# MCU_USB.net
KiCad netlist of a schematic drawn in Altium Designer
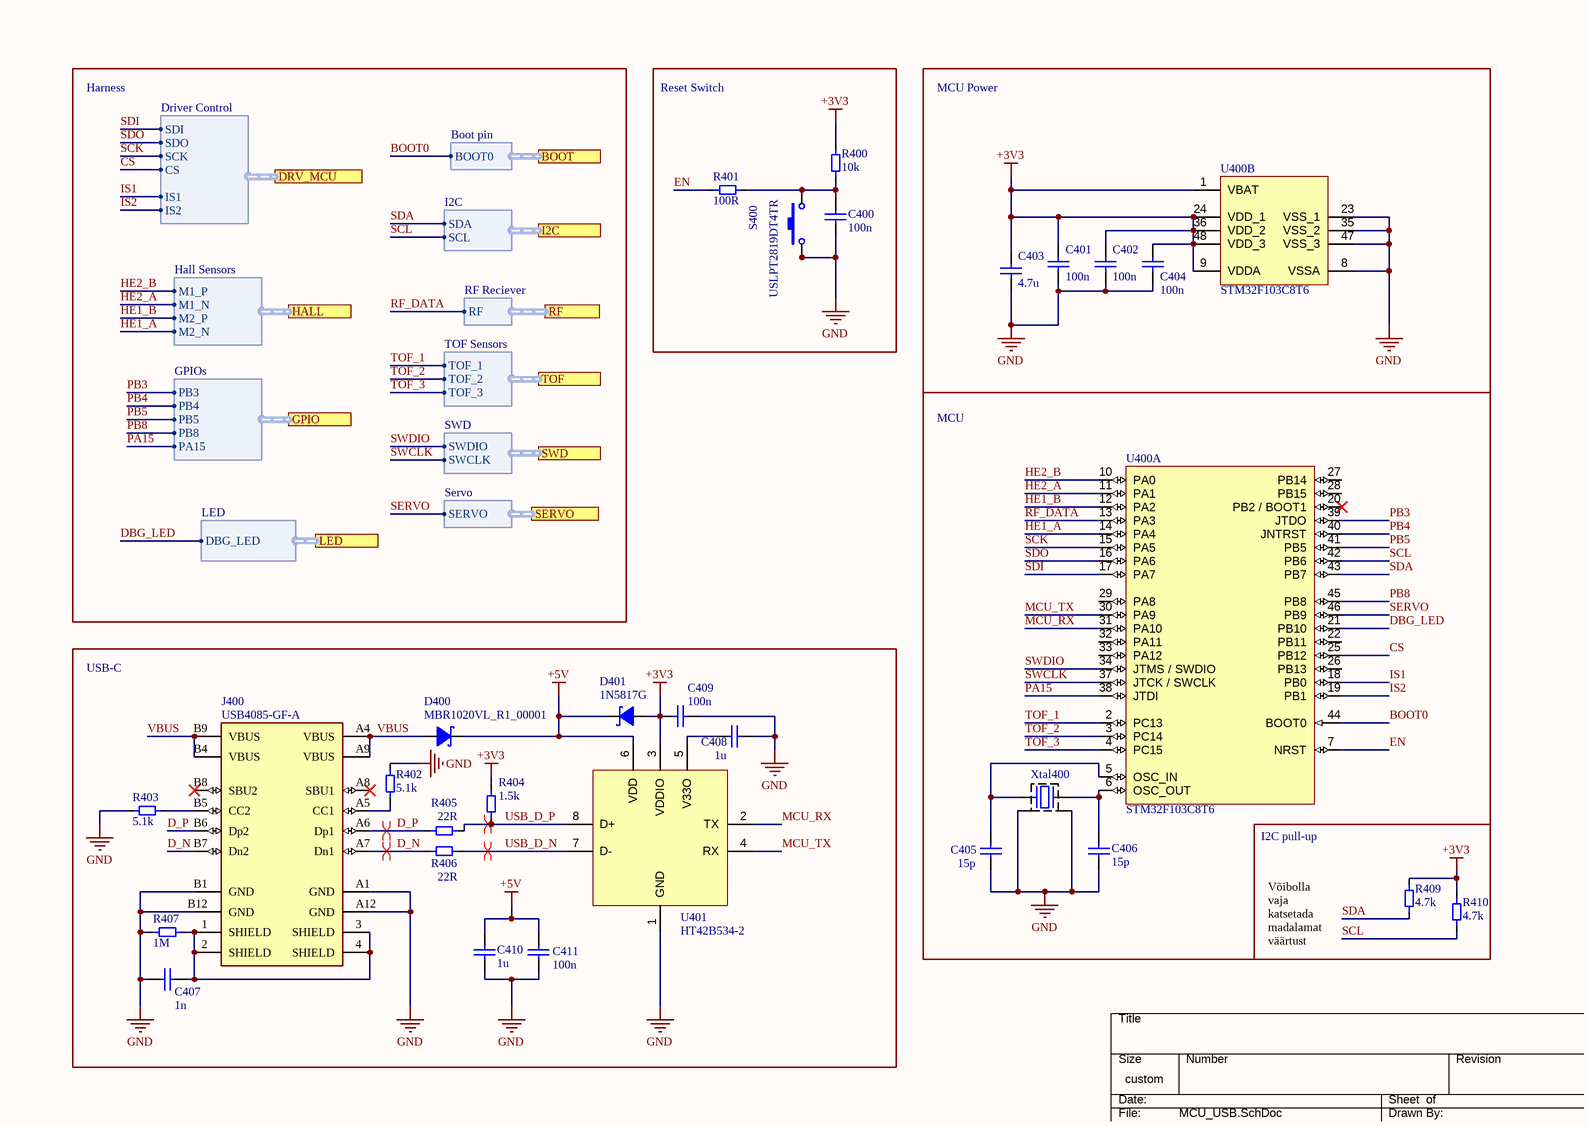
[diagram p0: MCU_USB.SchDoc]

(export (version "E")
  (design (tool "Eeschema 10.0.6"))
  (components
    (comp (ref "C400")
      (value "100n")
      (footprint "MLCC_0603_M")
      (description "MLCC, 0603, 100n, 10%, 50V, X7R")
      (fields (field (name "VOLTAGE") "50V") (field (name "TOLERANCE") "10%"))
      (libsource (lib "Krakul Vault") (part "CAPACITOR_NONPOL_IEC"))
    )
    (comp (ref "C401")
      (value "100n")
      (footprint "MLCC_0603_M")
      (description "MLCC, 0603, 100n, 10%, 50V, X7R")
      (fields (field (name "VOLTAGE") "50V") (field (name "TOLERANCE") "10%"))
      (libsource (lib "Krakul Vault") (part "CAPACITOR_NONPOL_IEC"))
    )
    (comp (ref "C402")
      (value "100n")
      (footprint "MLCC_0603_M")
      (description "MLCC, 0603, 100n, 10%, 50V, X7R")
      (fields (field (name "VOLTAGE") "50V") (field (name "TOLERANCE") "10%"))
      (libsource (lib "Krakul Vault") (part "CAPACITOR_NONPOL_IEC"))
    )
    (comp (ref "C403")
      (value "4.7u")
      (footprint "MLCC_0805_M")
      (description "MLCC, 0805, 4.7u, 20%, 50V, X5R")
      (fields (field (name "MANUFACTURER") "Any") (field (name "VOLTAGE") "50V"))
      (libsource (lib "Krakul Vault") (part "CAPACITOR_NONPOL_IEC"))
    )
    (comp (ref "C404")
      (value "100n")
      (footprint "MLCC_0603_M")
      (description "MLCC, 0603, 100n, 10%, 50V, X7R")
      (fields (field (name "VOLTAGE") "50V") (field (name "TOLERANCE") "10%"))
      (libsource (lib "Krakul Vault") (part "CAPACITOR_NONPOL_IEC"))
    )
    (comp (ref "C405")
      (value "15p")
      (footprint "MLCC_0402_M")
      (description "MLCC, 0402, 15p, 10%, 25V, C0G/NP0")
      (fields (field (name "MANUFACTURER") "Any") (field (name "TOLERANCE") "10%"))
      (libsource (lib "Krakul Vault") (part "CAPACITOR_NONPOL_IEC"))
    )
    (comp (ref "C406")
      (value "15p")
      (footprint "MLCC_0402_M")
      (description "MLCC, 0402, 15p, 10%, 25V, C0G/NP0")
      (fields (field (name "MANUFACTURER") "Any") (field (name "TOLERANCE") "10%"))
      (libsource (lib "Krakul Vault") (part "CAPACITOR_NONPOL_IEC"))
    )
    (comp (ref "C407")
      (value "1n")
      (footprint "MLCC_0603_M")
      (description "MLCC, 0603, 1n, 10%, 50V, X5R")
      (fields (field (name "MANUFACTURER") "Any") (field (name "TOLERANCE") "10%"))
      (libsource (lib "Krakul Vault") (part "CAPACITOR_NONPOL_IEC"))
    )
    (comp (ref "C408")
      (value "1u")
      (footprint "MLCC_0603_M")
      (description "MLCC, 0603, 1u, 10%, 50V, X5R")
      (fields (field (name "MANUFACTURER") "Any") (field (name "VOLTAGE") "50V"))
      (libsource (lib "Krakul Vault") (part "CAPACITOR_NONPOL_IEC"))
    )
    (comp (ref "C409")
      (value "100n")
      (footprint "MLCC_0603_M")
      (description "MLCC, 0603, 100n, 10%, 50V, X7R")
      (fields (field (name "VOLTAGE") "50V") (field (name "TOLERANCE") "10%"))
      (libsource (lib "Krakul Vault") (part "CAPACITOR_NONPOL_IEC"))
    )
    (comp (ref "C410")
      (value "1u")
      (footprint "MLCC_0603_M")
      (description "MLCC, 0603, 1u, 10%, 50V, X5R")
      (fields (field (name "MANUFACTURER") "Any") (field (name "VOLTAGE") "50V"))
      (libsource (lib "Krakul Vault") (part "CAPACITOR_NONPOL_IEC"))
    )
    (comp (ref "C411")
      (value "100n")
      (footprint "MLCC_0603_M")
      (description "MLCC, 0603, 100n, 10%, 50V, X7R")
      (fields (field (name "VOLTAGE") "50V") (field (name "TOLERANCE") "10%"))
      (libsource (lib "Krakul Vault") (part "CAPACITOR_NONPOL_IEC"))
    )
    (comp (ref "D400")
      (value "MBR1020VL_R1_00001")
      (footprint "FP-MBR1020VL_R1_00001-MFG")
      (description "Rectifier Diode, Schottky, 1 Phase, 1 Element, 1A, 20V V(RRM), Silicon")
      (fields (field (name "MANUFACTURER") "Panjit"))
      (libsource (lib "Krakul Vault") (part "Schottky generic 2 pins"))
    )
    (comp (ref "D401")
      (value "1N5817G")
      (footprint "SOD-323 based on 1N5817WS")
      (description "Rectifier Diode, Schottky, 1 Phase, 1 Element, 1A, 20V V(RRM), Silicon, DO-204AL")
      (fields (field (name "MANUFACTURER") "TWGMC / onsemi") (field (name "PART NUMBER") "1N5817WS"))
      (libsource (lib "Krakul Vault") (part "Schottky generic 2 pins"))
    )
    (comp (ref "J400")
      (value "USB4085-GF-A")
      (footprint "FP-USB4085-GF-A-MFG")
      (description "USB Connector, 16 Contact(s), Female, Right Angle, Solder Terminal, Locking, Receptacle")
      (fields (field (name "MANUFACTURER") "GCT") (field (name "PART NUMBER") "USB4800-03-A"))
      (libsource (lib "Krakul Vault") (part "USB4085-GF-A"))
    )
    (comp (ref "R400")
      (value "10k")
      (footprint "Resistor_0603_M")
      (description "Resistor, 0603, 10k, 1%, 1/10W")
      (fields (field (name "MANUFACTURER") "Any") (field (name "TOLERANCE") "1%"))
      (libsource (lib "Krakul Vault") (part "RESISTOR_GENERIC_IEC"))
    )
    (comp (ref "R401")
      (value "100R")
      (footprint "Resistor_0603_M")
      (description "Resistor, 0603, 100R, 1%, 1/10W")
      (fields (field (name "POWER") "100mW") (field (name "MANUFACTURER") "Any"))
      (libsource (lib "Krakul Vault") (part "RESISTOR_GENERIC_IEC"))
    )
    (comp (ref "R402")
      (value "5.1k")
      (footprint "Resistor_0603_M")
      (description "Resistor, 0603, 5.1k, 1%, 1/10W")
      (fields (field (name "POWER") "100mW") (field (name "MANUFACTURER") "Any"))
      (libsource (lib "Krakul Vault") (part "RESISTOR_GENERIC_IEC"))
    )
    (comp (ref "R403")
      (value "5.1k")
      (footprint "Resistor_0603_M")
      (description "Resistor, 0603, 5.1k, 1%, 1/10W")
      (fields (field (name "POWER") "100mW") (field (name "MANUFACTURER") "Any"))
      (libsource (lib "Krakul Vault") (part "RESISTOR_GENERIC_IEC"))
    )
    (comp (ref "R404")
      (value "1.5k")
      (footprint "Resistor_0603_M")
      (description "Resistor, 0603, 1.5k, 1%, 1/10W")
      (fields (field (name "MANUFACTURER") "Any") (field (name "POWER") "100mW"))
      (libsource (lib "Krakul Vault") (part "RESISTOR_GENERIC_IEC"))
    )
    (comp (ref "R405")
      (value "22R")
      (footprint "Resistor_0603_M")
      (description "Resistor, 0603, 22R, 1%, 1/10W")
      (fields (field (name "TOLERANCE") "1%") (field (name "MANUFACTURER") "Any"))
      (libsource (lib "Krakul Vault") (part "RESISTOR_GENERIC_IEC"))
    )
    (comp (ref "R406")
      (value "22R")
      (footprint "Resistor_0603_M")
      (description "Resistor, 0603, 22R, 1%, 1/10W")
      (fields (field (name "TOLERANCE") "1%") (field (name "MANUFACTURER") "Any"))
      (libsource (lib "Krakul Vault") (part "RESISTOR_GENERIC_IEC"))
    )
    (comp (ref "R407")
      (value "1M")
      (footprint "Resistor_1206_M")
      (description "Resistor, 1206, 1M, 1%, 1/4W")
      (fields (field (name "MANUFACTURER") "Any"))
      (libsource (lib "Krakul Vault") (part "RESISTOR_GENERIC_IEC"))
    )
    (comp (ref "R409")
      (value "4.7k")
      (footprint "Resistor_0603_M")
      (description "Resistor, 0603, 4.7k, 1%, 1/10W")
      (fields (field (name "MANUFACTURER") "Any") (field (name "POWER") "100mW"))
      (libsource (lib "Krakul Vault") (part "RESISTOR_GENERIC_IEC"))
    )
    (comp (ref "R410")
      (value "4.7k")
      (footprint "Resistor_0603_M")
      (description "Resistor, 0603, 4.7k, 1%, 1/10W")
      (fields (field (name "MANUFACTURER") "Any") (field (name "POWER") "100mW"))
      (libsource (lib "Krakul Vault") (part "RESISTOR_GENERIC_IEC"))
    )
    (comp (ref "S400")
      (value "USLPT2819DT4TR")
      (footprint "USLPT2819DT4TR-Footprint-1")
      (description "Keypad Switch, SPST, 0.05A, 1.96N, Solder Terminal, Panel Mount")
      (fields (field (name "MANUFACTURER") "TE Connectivity ALCOSWITCH Switches"))
      (libsource (lib "Krakul Vault") (part "Copy of Switch 4-pin"))
    )
    (comp (ref "U400")
      (value "STM32F103C8T6")
      (footprint "STM-LQFP48_M")
      (description "MCU 32-bit STM32F1 ARM Cortex M3 RISC 64KB Flash 2.5V/3.3V 48-Pin LQFP Tray")
      (fields (field (name "MANUFACTURER") "STMicroelectronics"))
      (libsource (lib "") (part "MC-ARM-STM32F103X4_6-SQ48_1"))
    )
    (comp (ref "U401")
      (value "HT42B534-2")
      (footprint "SOP-8 150mil")
      (description "USB to UART 3Mbps USB 2.0 SOP-8 Interface Controllers RoHS")
      (fields (field (name "MANUFACTURER") "HOLTEK"))
      (libsource (lib "Krakul Vault") (part "HT42B534-2"))
    )
    (comp (ref "Xtal400")
      (value "ABM11-16.000MHZ-12-N1G-T")
      (footprint "FP-ABM11-MFG")
      (description "Crystal 16MHz ±10ppm (Tol) ±15ppm (Stability) 12pF FUND 150Ohm 4-Pin Ultra Mini-CSMD T/R")
      (fields (field (name "MANUFACTURER") "Abracon LLC") (field (name "TOLERANCE") "0.001%"))
      (libsource (lib "Krakul Vault") (part "Crystal 4 pins"))
    )
  )
  (nets
    (net (code "15") (name "+3V3") (class "Default")
      (node (ref "C401") (pin "1") (pinfunction "1_1") (pintype "passive"))
      (node (ref "C402") (pin "1") (pinfunction "1_1") (pintype "passive"))
      (node (ref "C403") (pin "2") (pinfunction "2_2") (pintype "passive"))
      (node (ref "C404") (pin "1") (pinfunction "1_1") (pintype "passive"))
      (node (ref "C409") (pin "1") (pinfunction "1_1") (pintype "passive"))
      (node (ref "D401") (pin "2") (pinfunction "A_2") (pintype "passive"))
      (node (ref "R400") (pin "2") (pinfunction "2_2") (pintype "passive"))
      (node (ref "R404") (pin "2") (pinfunction "2_2") (pintype "passive"))
      (node (ref "R409") (pin "2") (pinfunction "2_2") (pintype "passive"))
      (node (ref "R410") (pin "2") (pinfunction "2_2") (pintype "passive"))
      (node (ref "U400") (pin "1") (pinfunction "VBAT_1") (pintype "power_in"))
      (node (ref "U400") (pin "24") (pinfunction "VDD_1_24") (pintype "power_in"))
      (node (ref "U400") (pin "36") (pinfunction "VDD_2_36") (pintype "power_in"))
      (node (ref "U400") (pin "48") (pinfunction "VDD_3_48") (pintype "power_in"))
      (node (ref "U400") (pin "9") (pinfunction "VDDA_9") (pintype "power_in"))
      (node (ref "U401") (pin "3") (pinfunction "VDDIO_3") (pintype "passive"))
    )
    (net (code "16") (name "+5V") (class "Default")
      (node (ref "C410") (pin "2") (pinfunction "2_2") (pintype "passive"))
      (node (ref "C411") (pin "1") (pinfunction "1_1") (pintype "passive"))
      (node (ref "D400") (pin "1") (pinfunction "C_1") (pintype "passive"))
      (node (ref "D401") (pin "1") (pinfunction "C_1") (pintype "passive"))
      (node (ref "U401") (pin "6") (pinfunction "VDD_6") (pintype "passive"))
    )
    (net (code "17") (name "/BOOT0") (class "Default")
      (node (ref "U400") (pin "44") (pinfunction "BOOT0_44") (pintype "input"))
    )
    (net (code "18") (name "/CS") (class "Default")
      (node (ref "U400") (pin "25") (pinfunction "PB12_25") (pintype "bidirectional"))
    )
    (net (code "19") (name "/DBG_LED") (class "Default")
      (node (ref "U400") (pin "21") (pinfunction "PB10_21") (pintype "bidirectional"))
    )
    (net (code "20") (name "/D_N") (class "Default")
      (node (ref "J400") (pin "A7") (pinfunction "Dn1_A7") (pintype "bidirectional"))
      (node (ref "J400") (pin "B7") (pinfunction "Dn2_B7") (pintype "bidirectional"))
      (node (ref "R406") (pin "1") (pinfunction "1_1") (pintype "passive"))
    )
    (net (code "21") (name "/D_P") (class "Default")
      (node (ref "J400") (pin "A6") (pinfunction "Dp1_A6") (pintype "bidirectional"))
      (node (ref "J400") (pin "B6") (pinfunction "Dp2_B6") (pintype "bidirectional"))
      (node (ref "R405") (pin "1") (pinfunction "1_1") (pintype "passive"))
    )
    (net (code "22") (name "/EN") (class "Default")
      (node (ref "R401") (pin "2") (pinfunction "2_2") (pintype "passive"))
      (node (ref "U400") (pin "7") (pinfunction "NRST_7") (pintype "bidirectional"))
    )
    (net (code "23") (name "/HE1_A") (class "Default")
      (node (ref "U400") (pin "14") (pinfunction "PA4_14") (pintype "bidirectional"))
    )
    (net (code "24") (name "/HE1_B") (class "Default")
      (node (ref "U400") (pin "12") (pinfunction "PA2_12") (pintype "bidirectional"))
    )
    (net (code "25") (name "/HE2_A") (class "Default")
      (node (ref "U400") (pin "11") (pinfunction "PA1_11") (pintype "bidirectional"))
    )
    (net (code "26") (name "/HE2_B") (class "Default")
      (node (ref "U400") (pin "10") (pinfunction "PA0_10") (pintype "bidirectional"))
    )
    (net (code "27") (name "/IS1") (class "Default")
      (node (ref "U400") (pin "18") (pinfunction "PB0_18") (pintype "bidirectional"))
    )
    (net (code "28") (name "/IS2") (class "Default")
      (node (ref "U400") (pin "19") (pinfunction "PB1_19") (pintype "bidirectional"))
    )
    (net (code "29") (name "/MCU_RX") (class "Default")
      (node (ref "U400") (pin "31") (pinfunction "PA10_31") (pintype "bidirectional"))
      (node (ref "U401") (pin "2") (pinfunction "TX_2") (pintype "passive"))
    )
    (net (code "30") (name "/MCU_TX") (class "Default")
      (node (ref "U400") (pin "30") (pinfunction "PA9_30") (pintype "bidirectional"))
      (node (ref "U401") (pin "4") (pinfunction "RX_4") (pintype "passive"))
    )
    (net (code "31") (name "/PA15") (class "Default")
      (node (ref "U400") (pin "38") (pinfunction "JTDI_38") (pintype "bidirectional"))
    )
    (net (code "32") (name "/PB3") (class "Default")
      (node (ref "U400") (pin "39") (pinfunction "JTDO_39") (pintype "bidirectional"))
    )
    (net (code "33") (name "/PB4") (class "Default")
      (node (ref "U400") (pin "40") (pinfunction "JNTRST_40") (pintype "bidirectional"))
    )
    (net (code "34") (name "/PB5") (class "Default")
      (node (ref "U400") (pin "41") (pinfunction "PB5_41") (pintype "bidirectional"))
    )
    (net (code "35") (name "/PB8") (class "Default")
      (node (ref "U400") (pin "45") (pinfunction "PB8_45") (pintype "bidirectional"))
    )
    (net (code "36") (name "/RF_DATA") (class "Default")
      (node (ref "U400") (pin "13") (pinfunction "PA3_13") (pintype "bidirectional"))
    )
    (net (code "37") (name "/SCK") (class "Default")
      (node (ref "U400") (pin "15") (pinfunction "PA5_15") (pintype "bidirectional"))
    )
    (net (code "38") (name "/SCL") (class "Default")
      (node (ref "R410") (pin "1") (pinfunction "1_1") (pintype "passive"))
      (node (ref "U400") (pin "42") (pinfunction "PB6_42") (pintype "bidirectional"))
    )
    (net (code "39") (name "/SDA") (class "Default")
      (node (ref "R409") (pin "1") (pinfunction "1_1") (pintype "passive"))
      (node (ref "U400") (pin "43") (pinfunction "PB7_43") (pintype "bidirectional"))
    )
    (net (code "40") (name "/SDI") (class "Default")
      (node (ref "U400") (pin "17") (pinfunction "PA7_17") (pintype "bidirectional"))
    )
    (net (code "41") (name "/SDO") (class "Default")
      (node (ref "U400") (pin "16") (pinfunction "PA6_16") (pintype "bidirectional"))
    )
    (net (code "42") (name "/SERVO") (class "Default")
      (node (ref "U400") (pin "46") (pinfunction "PB9_46") (pintype "bidirectional"))
    )
    (net (code "43") (name "/SWCLK") (class "Default")
      (node (ref "U400") (pin "37") (pinfunction "JTCK_/_SWCLK_37") (pintype "bidirectional"))
    )
    (net (code "44") (name "/SWDIO") (class "Default")
      (node (ref "U400") (pin "34") (pinfunction "JTMS_/_SWDIO_34") (pintype "bidirectional"))
    )
    (net (code "45") (name "/TOF_1") (class "Default")
      (node (ref "U400") (pin "2") (pinfunction "PC13_2") (pintype "bidirectional"))
    )
    (net (code "46") (name "/TOF_2") (class "Default")
      (node (ref "U400") (pin "3") (pinfunction "PC14_3") (pintype "bidirectional"))
    )
    (net (code "47") (name "/TOF_3") (class "Default")
      (node (ref "U400") (pin "4") (pinfunction "PC15_4") (pintype "bidirectional"))
    )
    (net (code "48") (name "/USB_D_N") (class "Default")
      (node (ref "R406") (pin "2") (pinfunction "2_2") (pintype "passive"))
      (node (ref "U401") (pin "7") (pinfunction "D-_7") (pintype "passive"))
    )
    (net (code "49") (name "/USB_D_P") (class "Default")
      (node (ref "R404") (pin "1") (pinfunction "1_1") (pintype "passive"))
      (node (ref "R405") (pin "2") (pinfunction "2_2") (pintype "passive"))
      (node (ref "U401") (pin "8") (pinfunction "D+_8") (pintype "passive"))
    )
    (net (code "50") (name "/VBUS") (class "Default")
      (node (ref "D400") (pin "2") (pinfunction "A_2") (pintype "passive"))
      (node (ref "J400") (pin "A4") (pinfunction "VBUS_A4") (pintype "power_in"))
      (node (ref "J400") (pin "A9") (pinfunction "VBUS_A9") (pintype "power_in"))
      (node (ref "J400") (pin "B4") (pinfunction "VBUS_B4") (pintype "power_in"))
      (node (ref "J400") (pin "B9") (pinfunction "VBUS_B9") (pintype "power_in"))
    )
    (net (code "61") (name "GND") (class "Default")
      (node (ref "C400") (pin "1") (pinfunction "1_1") (pintype "passive"))
      (node (ref "C401") (pin "2") (pinfunction "2_2") (pintype "passive"))
      (node (ref "C402") (pin "2") (pinfunction "2_2") (pintype "passive"))
      (node (ref "C403") (pin "1") (pinfunction "1_1") (pintype "passive"))
      (node (ref "C404") (pin "2") (pinfunction "2_2") (pintype "passive"))
      (node (ref "C405") (pin "1") (pinfunction "1_1") (pintype "passive"))
      (node (ref "C406") (pin "1") (pinfunction "1_1") (pintype "passive"))
      (node (ref "C407") (pin "1") (pinfunction "1_1") (pintype "passive"))
      (node (ref "C408") (pin "2") (pinfunction "2_2") (pintype "passive"))
      (node (ref "C409") (pin "2") (pinfunction "2_2") (pintype "passive"))
      (node (ref "C410") (pin "1") (pinfunction "1_1") (pintype "passive"))
      (node (ref "C411") (pin "2") (pinfunction "2_2") (pintype "passive"))
      (node (ref "J400") (pin "A1") (pinfunction "GND_A1") (pintype "power_in"))
      (node (ref "J400") (pin "A12") (pinfunction "GND_A12") (pintype "power_in"))
      (node (ref "J400") (pin "B1") (pinfunction "GND_B1") (pintype "power_in"))
      (node (ref "J400") (pin "B12") (pinfunction "GND_B12") (pintype "power_in"))
      (node (ref "R402") (pin "2") (pinfunction "2_2") (pintype "passive"))
      (node (ref "R403") (pin "1") (pinfunction "1_1") (pintype "passive"))
      (node (ref "R407") (pin "2") (pinfunction "2_2") (pintype "passive"))
      (node (ref "S400") (pin "1") (pinfunction "1_1") (pintype "passive"))
      (node (ref "S400") (pin "2") (pinfunction "2_2") (pintype "passive"))
      (node (ref "U400") (pin "23") (pinfunction "VSS_1_23") (pintype "power_in"))
      (node (ref "U400") (pin "35") (pinfunction "VSS_2_35") (pintype "power_in"))
      (node (ref "U400") (pin "47") (pinfunction "VSS_3_47") (pintype "power_in"))
      (node (ref "U400") (pin "8") (pinfunction "VSSA_8") (pintype "power_in"))
      (node (ref "U401") (pin "1") (pinfunction "GND_1") (pintype "passive"))
      (node (ref "Xtal400") (pin "2") (pinfunction "2_2") (pintype "power_in"))
      (node (ref "Xtal400") (pin "4") (pinfunction "4_4") (pintype "power_in"))
    )
    (net (code "62") (name "Net-(C400-Pad2)") (class "Default")
      (node (ref "C400") (pin "2") (pinfunction "2_2") (pintype "passive"))
      (node (ref "R400") (pin "1") (pinfunction "1_1") (pintype "passive"))
      (node (ref "R401") (pin "1") (pinfunction "1_1") (pintype "passive"))
      (node (ref "S400") (pin "3") (pinfunction "3_3") (pintype "passive"))
      (node (ref "S400") (pin "4") (pinfunction "4_4") (pintype "passive"))
    )
    (net (code "63") (name "Net-(C407-Pad2)") (class "Default")
      (node (ref "C407") (pin "2") (pinfunction "2_2") (pintype "passive"))
      (node (ref "J400") (pin "1") (pinfunction "SHIELD_1") (pintype "passive"))
      (node (ref "J400") (pin "2") (pinfunction "SHIELD_2") (pintype "passive"))
      (node (ref "J400") (pin "3") (pinfunction "SHIELD_3") (pintype "passive"))
      (node (ref "J400") (pin "4") (pinfunction "SHIELD_4") (pintype "passive"))
      (node (ref "R407") (pin "1") (pinfunction "1_1") (pintype "passive"))
    )
    (net (code "64") (name "Net-(J400-CC1)") (class "Default")
      (node (ref "J400") (pin "A5") (pinfunction "CC1_A5") (pintype "bidirectional"))
      (node (ref "R402") (pin "1") (pinfunction "1_1") (pintype "passive"))
    )
    (net (code "65") (name "Net-(J400-CC2)") (class "Default")
      (node (ref "J400") (pin "B5") (pinfunction "CC2_B5") (pintype "bidirectional"))
      (node (ref "R403") (pin "2") (pinfunction "2_2") (pintype "passive"))
    )
    (net (code "66") (name "Net-(U400A-OSC_IN)") (class "Default")
      (node (ref "C405") (pin "2") (pinfunction "2_2") (pintype "passive"))
      (node (ref "U400") (pin "5") (pinfunction "OSC_IN_5") (pintype "bidirectional"))
      (node (ref "Xtal400") (pin "1") (pinfunction "1_1") (pintype "passive"))
    )
    (net (code "67") (name "Net-(U400A-OSC_OUT)") (class "Default")
      (node (ref "C406") (pin "2") (pinfunction "2_2") (pintype "passive"))
      (node (ref "U400") (pin "6") (pinfunction "OSC_OUT_6") (pintype "bidirectional"))
      (node (ref "Xtal400") (pin "3") (pinfunction "3_3") (pintype "passive"))
    )
    (net (code "68") (name "Net-(U401-V33O)") (class "Default")
      (node (ref "C408") (pin "1") (pinfunction "1_1") (pintype "passive"))
      (node (ref "U401") (pin "5") (pinfunction "V33O_5") (pintype "passive"))
    )
    (net (code "69") (name "unconnected-(J400-SBU1-PadA8)") (class "Default")
      (node (ref "J400") (pin "A8") (pinfunction "SBU1_A8") (pintype "bidirectional+no_connect"))
    )
    (net (code "70") (name "unconnected-(J400-SBU2-PadB8)") (class "Default")
      (node (ref "J400") (pin "B8") (pinfunction "SBU2_B8") (pintype "bidirectional+no_connect"))
    )
    (net (code "71") (name "unconnected-(U400A-PA8-Pad29)") (class "Default")
      (node (ref "U400") (pin "29") (pinfunction "PA8_29") (pintype "bidirectional"))
    )
    (net (code "72") (name "unconnected-(U400A-PA11-Pad32)") (class "Default")
      (node (ref "U400") (pin "32") (pinfunction "PA11_32") (pintype "bidirectional"))
    )
    (net (code "73") (name "unconnected-(U400A-PA12-Pad33)") (class "Default")
      (node (ref "U400") (pin "33") (pinfunction "PA12_33") (pintype "bidirectional"))
    )
    (net (code "74") (name "unconnected-(U400A-PB2_{slash}_BOOT1-Pad20)") (class "Default")
      (node (ref "U400") (pin "20") (pinfunction "PB2_/_BOOT1_20") (pintype "bidirectional+no_connect"))
    )
    (net (code "75") (name "unconnected-(U400A-PB11-Pad22)") (class "Default")
      (node (ref "U400") (pin "22") (pinfunction "PB11_22") (pintype "bidirectional"))
    )
    (net (code "76") (name "unconnected-(U400A-PB13-Pad26)") (class "Default")
      (node (ref "U400") (pin "26") (pinfunction "PB13_26") (pintype "bidirectional"))
    )
    (net (code "77") (name "unconnected-(U400A-PB14-Pad27)") (class "Default")
      (node (ref "U400") (pin "27") (pinfunction "PB14_27") (pintype "bidirectional"))
    )
    (net (code "78") (name "unconnected-(U400A-PB15-Pad28)") (class "Default")
      (node (ref "U400") (pin "28") (pinfunction "PB15_28") (pintype "bidirectional"))
    )
  )
)
